# switch_vn9e30f.net
KiCad netlist of a schematic drawn in Altium Designer
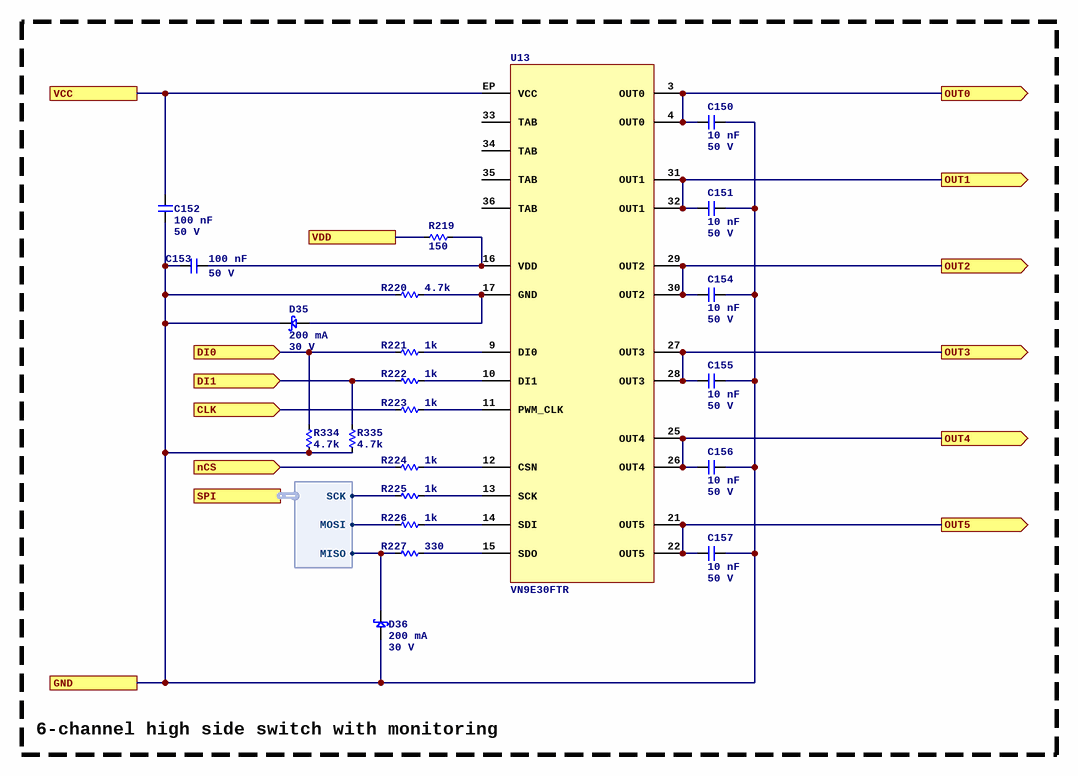
[diagram p0: switch_vn9e30f.SchDoc]

(export (version "E")
  (design (tool "Eeschema 10.0.6"))
  (components
    (comp (ref "C150")
      (value "CL05B103KB5NNNC")
      (footprint "C0402")
      (fields
        (field (name "CAPACITANCE") "10 nF")
        (field (name "MANUFACTURER") "Samsung Electro-Mechanics")
        (field (name "VOLTAGE RATING") "50 V")
      )
      (libsource (lib "database") (part "__template_cap"))
    )
    (comp (ref "C151")
      (value "CL05B103KB5NNNC")
      (footprint "C0402")
      (fields
        (field (name "CAPACITANCE") "10 nF")
        (field (name "MANUFACTURER") "Samsung Electro-Mechanics")
        (field (name "VOLTAGE RATING") "50 V")
      )
      (libsource (lib "database") (part "__template_cap"))
    )
    (comp (ref "C152")
      (value "CL05B104KB54PNC")
      (footprint "C0402")
      (fields
        (field (name "CAPACITANCE") "100 nF")
        (field (name "MANUFACTURER") "Samsung Electro-Mechanics")
        (field (name "VOLTAGE RATING") "50 V")
      )
      (libsource (lib "database") (part "__template_cap"))
    )
    (comp (ref "C153")
      (value "CL05B104KB54PNC")
      (footprint "C0402")
      (fields
        (field (name "CAPACITANCE") "100 nF")
        (field (name "MANUFACTURER") "Samsung Electro-Mechanics")
        (field (name "VOLTAGE RATING") "50 V")
      )
      (libsource (lib "database") (part "__template_cap"))
    )
    (comp (ref "C154")
      (value "CL05B103KB5NNNC")
      (footprint "C0402")
      (fields
        (field (name "CAPACITANCE") "10 nF")
        (field (name "MANUFACTURER") "Samsung Electro-Mechanics")
        (field (name "VOLTAGE RATING") "50 V")
      )
      (libsource (lib "database") (part "__template_cap"))
    )
    (comp (ref "C155")
      (value "CL05B103KB5NNNC")
      (footprint "C0402")
      (fields
        (field (name "CAPACITANCE") "10 nF")
        (field (name "MANUFACTURER") "Samsung Electro-Mechanics")
        (field (name "VOLTAGE RATING") "50 V")
      )
      (libsource (lib "database") (part "__template_cap"))
    )
    (comp (ref "C156")
      (value "CL05B103KB5NNNC")
      (footprint "C0402")
      (fields
        (field (name "CAPACITANCE") "10 nF")
        (field (name "MANUFACTURER") "Samsung Electro-Mechanics")
        (field (name "VOLTAGE RATING") "50 V")
      )
      (libsource (lib "database") (part "__template_cap"))
    )
    (comp (ref "C157")
      (value "CL05B103KB5NNNC")
      (footprint "C0402")
      (fields
        (field (name "CAPACITANCE") "10 nF")
        (field (name "MANUFACTURER") "Samsung Electro-Mechanics")
        (field (name "VOLTAGE RATING") "50 V")
      )
      (libsource (lib "database") (part "__template_cap"))
    )
    (comp (ref "D35")
      (value "BAT54XV2T1G")
      (footprint "SOD523")
      (description "ON Semi BAT54XV2T1G; SMT Schottky Diode; 30V 200mA; 5ns; 2-Pin SOD-523")
      (fields
        (field (name "MANUFACTURER") "onsemi")
        (field (name "CURRENT") "200 mA")
        (field (name "VR") "30 V")
      )
      (libsource (lib "database") (part "__template_diode_schottky"))
    )
    (comp (ref "D36")
      (value "BAT54XV2T1G")
      (footprint "SOD523")
      (description "ON Semi BAT54XV2T1G; SMT Schottky Diode; 30V 200mA; 5ns; 2-Pin SOD-523")
      (fields
        (field (name "MANUFACTURER") "onsemi")
        (field (name "CURRENT") "200 mA")
        (field (name "VR") "30 V")
      )
      (libsource (lib "database") (part "__template_diode_schottky"))
    )
    (comp (ref "R219")
      (value "150")
      (footprint "R0402")
      (fields
        (field (name "TOLERANCE") "1%")
        (field (name "MANUFACTURER PART NUMBER") "0402WGF1500TCE")
        (field (name "MANUFACTURER") "UNI-ROYAL(Uniroyal Elec)")
      )
      (libsource (lib "database") (part "__template_resistor"))
    )
    (comp (ref "R220")
      (value "4.7k")
      (footprint "R0402")
      (fields
        (field (name "TOLERANCE") "1%")
        (field (name "MANUFACTURER PART NUMBER") "0402WGF4701TCE")
        (field (name "MANUFACTURER") "UNI-ROYAL(Uniroyal Elec)")
      )
      (libsource (lib "database") (part "__template_resistor"))
    )
    (comp (ref "R221")
      (value "1k")
      (footprint "R0402")
      (fields
        (field (name "TOLERANCE") "1%")
        (field (name "MANUFACTURER PART NUMBER") "0402WGF1001TCE")
        (field (name "MANUFACTURER") "UNI-ROYAL(Uniroyal Elec)")
      )
      (libsource (lib "database") (part "__template_resistor"))
    )
    (comp (ref "R222")
      (value "1k")
      (footprint "R0402")
      (fields
        (field (name "TOLERANCE") "1%")
        (field (name "MANUFACTURER PART NUMBER") "0402WGF1001TCE")
        (field (name "MANUFACTURER") "UNI-ROYAL(Uniroyal Elec)")
      )
      (libsource (lib "database") (part "__template_resistor"))
    )
    (comp (ref "R223")
      (value "1k")
      (footprint "R0402")
      (fields
        (field (name "TOLERANCE") "1%")
        (field (name "MANUFACTURER PART NUMBER") "0402WGF1001TCE")
        (field (name "MANUFACTURER") "UNI-ROYAL(Uniroyal Elec)")
      )
      (libsource (lib "database") (part "__template_resistor"))
    )
    (comp (ref "R224")
      (value "1k")
      (footprint "R0402")
      (fields
        (field (name "TOLERANCE") "1%")
        (field (name "MANUFACTURER PART NUMBER") "0402WGF1001TCE")
        (field (name "MANUFACTURER") "UNI-ROYAL(Uniroyal Elec)")
      )
      (libsource (lib "database") (part "__template_resistor"))
    )
    (comp (ref "R225")
      (value "1k")
      (footprint "R0402")
      (fields
        (field (name "TOLERANCE") "1%")
        (field (name "MANUFACTURER PART NUMBER") "0402WGF1001TCE")
        (field (name "MANUFACTURER") "UNI-ROYAL(Uniroyal Elec)")
      )
      (libsource (lib "database") (part "__template_resistor"))
    )
    (comp (ref "R226")
      (value "1k")
      (footprint "R0402")
      (fields
        (field (name "TOLERANCE") "1%")
        (field (name "MANUFACTURER PART NUMBER") "0402WGF1001TCE")
        (field (name "MANUFACTURER") "UNI-ROYAL(Uniroyal Elec)")
      )
      (libsource (lib "database") (part "__template_resistor"))
    )
    (comp (ref "R227")
      (value "330")
      (footprint "R0402")
      (fields
        (field (name "TOLERANCE") "1%")
        (field (name "MANUFACTURER PART NUMBER") "0402WGF3300TCE")
        (field (name "MANUFACTURER") "UNI-ROYAL(Uniroyal Elec)")
      )
      (libsource (lib "database") (part "__template_resistor"))
    )
    (comp (ref "R334")
      (value "4.7k")
      (footprint "R0402")
      (fields
        (field (name "TOLERANCE") "1%")
        (field (name "MANUFACTURER PART NUMBER") "0402WGF4701TCE")
        (field (name "MANUFACTURER") "UNI-ROYAL(Uniroyal Elec)")
      )
      (libsource (lib "database") (part "__template_resistor"))
    )
    (comp (ref "R335")
      (value "4.7k")
      (footprint "R0402")
      (fields
        (field (name "TOLERANCE") "1%")
        (field (name "MANUFACTURER PART NUMBER") "0402WGF4701TCE")
        (field (name "MANUFACTURER") "UNI-ROYAL(Uniroyal Elec)")
      )
      (libsource (lib "database") (part "__template_resistor"))
    )
    (comp (ref "U13")
      (value "VN9E30FTR")
      (footprint "ST_ECOPACK_QFN50P600X600X90-32N")
      (description "Power Switch/Driver 1:6 N-Channel 35A 32-QFN (6x6)")
      (fields (field (name "MANUFACTURER") "STMicroelectronics"))
      (libsource (lib "database") (part "VN9E30FTR"))
    )
  )
  (nets
    (net (code "2") (name "/CLK") (class "Default") (node (ref "R223") (pin "2") (pintype "passive")))
    (net (code "3") (name "/DI0") (class "Default")
      (node (ref "R221") (pin "2") (pintype "passive"))
      (node (ref "R334") (pin "1") (pintype "passive"))
    )
    (net (code "4") (name "/DI1") (class "Default")
      (node (ref "R222") (pin "2") (pintype "passive"))
      (node (ref "R335") (pin "1") (pintype "passive"))
    )
    (net (code "5") (name "/GND") (class "Default")
      (node (ref "C150") (pin "2") (pintype "passive"))
      (node (ref "C151") (pin "2") (pintype "passive"))
      (node (ref "C152") (pin "2") (pintype "passive"))
      (node (ref "C153") (pin "2") (pintype "passive"))
      (node (ref "C154") (pin "2") (pintype "passive"))
      (node (ref "C155") (pin "2") (pintype "passive"))
      (node (ref "C156") (pin "2") (pintype "passive"))
      (node (ref "C157") (pin "2") (pintype "passive"))
      (node (ref "D35") (pin "2") (pintype "passive"))
      (node (ref "D36") (pin "1") (pintype "passive"))
      (node (ref "R220") (pin "2") (pintype "passive"))
      (node (ref "R334") (pin "2") (pintype "passive"))
      (node (ref "R335") (pin "2") (pintype "passive"))
    )
    (net (code "6") (name "/MISO") (class "Default")
      (node (ref "D36") (pin "2") (pintype "passive"))
      (node (ref "R227") (pin "1") (pintype "passive"))
    )
    (net (code "7") (name "/MOSI") (class "Default") (node (ref "R226") (pin "2") (pintype "passive")))
    (net (code "8") (name "/OUT0") (class "Default")
      (node (ref "C150") (pin "1") (pintype "passive"))
      (node (ref "U13") (pin "3") (pinfunction "OUT0_3") (pintype "passive"))
      (node (ref "U13") (pin "4") (pinfunction "OUT0_4") (pintype "passive"))
    )
    (net (code "9") (name "/OUT1") (class "Default")
      (node (ref "C151") (pin "1") (pintype "passive"))
      (node (ref "U13") (pin "31") (pinfunction "OUT1_31") (pintype "passive"))
      (node (ref "U13") (pin "32") (pinfunction "OUT1_32") (pintype "passive"))
    )
    (net (code "10") (name "/OUT2") (class "Default")
      (node (ref "C154") (pin "1") (pintype "passive"))
      (node (ref "U13") (pin "29") (pinfunction "OUT2_29") (pintype "passive"))
      (node (ref "U13") (pin "30") (pinfunction "OUT2_30") (pintype "passive"))
    )
    (net (code "11") (name "/OUT3") (class "Default")
      (node (ref "C155") (pin "1") (pintype "passive"))
      (node (ref "U13") (pin "27") (pinfunction "OUT3_27") (pintype "passive"))
      (node (ref "U13") (pin "28") (pinfunction "OUT3_28") (pintype "passive"))
    )
    (net (code "12") (name "/OUT4") (class "Default")
      (node (ref "C156") (pin "1") (pintype "passive"))
      (node (ref "U13") (pin "25") (pinfunction "OUT4_25") (pintype "passive"))
      (node (ref "U13") (pin "26") (pinfunction "OUT4_26") (pintype "passive"))
    )
    (net (code "13") (name "/OUT5") (class "Default")
      (node (ref "C157") (pin "1") (pintype "passive"))
      (node (ref "U13") (pin "21") (pinfunction "OUT5_21") (pintype "passive"))
      (node (ref "U13") (pin "22") (pinfunction "OUT5_22") (pintype "passive"))
    )
    (net (code "14") (name "/SCK") (class "Default") (node (ref "R225") (pin "2") (pintype "passive")))
    (net (code "15") (name "/VCC") (class "Default")
      (node (ref "C152") (pin "1") (pintype "passive"))
      (node (ref "U13") (pin "EP") (pinfunction "VCC_EP") (pintype "passive"))
    )
    (net (code "16") (name "/VDD") (class "Default") (node (ref "R219") (pin "1") (pintype "passive")))
    (net (code "17") (name "/nCS") (class "Default") (node (ref "R224") (pin "2") (pintype "passive")))
    (net (code "19") (name "Net-(U13-CSN)") (class "Default")
      (node (ref "R224") (pin "1") (pintype "passive"))
      (node (ref "U13") (pin "12") (pinfunction "CSN_12") (pintype "passive"))
    )
    (net (code "20") (name "Net-(U13-DI0)") (class "Default")
      (node (ref "R221") (pin "1") (pintype "passive"))
      (node (ref "U13") (pin "9") (pinfunction "DI0_9") (pintype "passive"))
    )
    (net (code "21") (name "Net-(U13-DI1)") (class "Default")
      (node (ref "R222") (pin "1") (pintype "passive"))
      (node (ref "U13") (pin "10") (pinfunction "DI1_10") (pintype "passive"))
    )
    (net (code "22") (name "Net-(U13-GND)") (class "Default")
      (node (ref "D35") (pin "1") (pintype "passive"))
      (node (ref "R220") (pin "1") (pintype "passive"))
      (node (ref "U13") (pin "17") (pinfunction "GND_17") (pintype "passive"))
    )
    (net (code "23") (name "Net-(U13-PWM_CLK)") (class "Default")
      (node (ref "R223") (pin "1") (pintype "passive"))
      (node (ref "U13") (pin "11") (pinfunction "PWM_CLK_11") (pintype "passive"))
    )
    (net (code "24") (name "Net-(U13-SCK)") (class "Default")
      (node (ref "R225") (pin "1") (pintype "passive"))
      (node (ref "U13") (pin "13") (pinfunction "SCK_13") (pintype "passive"))
    )
    (net (code "25") (name "Net-(U13-SDI)") (class "Default")
      (node (ref "R226") (pin "1") (pintype "passive"))
      (node (ref "U13") (pin "14") (pinfunction "SDI_14") (pintype "passive"))
    )
    (net (code "26") (name "Net-(U13-SDO)") (class "Default")
      (node (ref "R227") (pin "2") (pintype "passive"))
      (node (ref "U13") (pin "15") (pinfunction "SDO_15") (pintype "passive"))
    )
    (net (code "27") (name "Net-(U13-VDD)") (class "Default")
      (node (ref "C153") (pin "1") (pintype "passive"))
      (node (ref "R219") (pin "2") (pintype "passive"))
      (node (ref "U13") (pin "16") (pinfunction "VDD_16") (pintype "passive"))
    )
    (net (code "28") (name "unconnected-(U13-TAB-Pad33)") (class "Default")
      (node (ref "U13") (pin "33") (pinfunction "TAB_33") (pintype "passive"))
    )
    (net (code "29") (name "unconnected-(U13-TAB-Pad34)") (class "Default")
      (node (ref "U13") (pin "34") (pinfunction "TAB_34") (pintype "passive"))
    )
    (net (code "30") (name "unconnected-(U13-TAB-Pad35)") (class "Default")
      (node (ref "U13") (pin "35") (pinfunction "TAB_35") (pintype "passive"))
    )
    (net (code "31") (name "unconnected-(U13-TAB-Pad36)") (class "Default")
      (node (ref "U13") (pin "36") (pinfunction "TAB_36") (pintype "passive"))
    )
  )
)
